# MAX485.net
KiCad netlist of a schematic drawn in Altium Designer
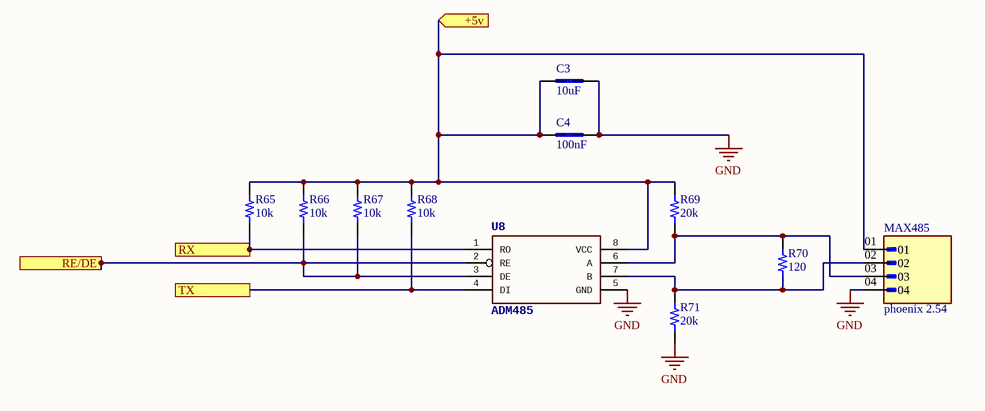
[diagram p0: MAX485.SchDoc]

(export (version "E")
  (design (tool "Eeschema 10.0.6"))
  (components
    (comp (ref "C3")
      (value "10uF")
      (footprint "CAP 0805_2012")
      (description "COMMERCIAL CHIP STD JAPAN BULK - FN TAPE/REEL, 7 INCH PAPER TAPE-0805")
      (fields (field (name "MP") "LD051C182KAB2A"))
      (libsource (lib "cap 0805") (part "LD051C182KAB2A"))
    )
    (comp (ref "C4")
      (value "100nF")
      (footprint "CAP 0805_2012")
      (description "COMMERCIAL CHIP STD JAPAN BULK - FN TAPE/REEL, 7 INCH PAPER TAPE-0805")
      (fields (field (name "MP") "LD051C182KAB2A"))
      (libsource (lib "cap 0805") (part "LD051C182KAB2A"))
    )
    (comp (ref "MAX485")
      (value "phoenix 2.54")
      (footprint "PHOENIX_1881574")
      (fields (field (name "MF") "{'manufacturer': u'Phoenix Contact'}") (field (name "MP") "1881574"))
      (libsource (lib "1881574") (part "1881574"))
    )
    (comp (ref "R65")
      (value "10k")
      (footprint "RES 0805_2012")
      (description "SMT Resistor")
      (libsource (lib "Resistor") (part "Res 0805"))
    )
    (comp (ref "R66")
      (value "10k")
      (footprint "RES 0805_2012")
      (description "SMT Resistor")
      (libsource (lib "Resistor") (part "Res 0805"))
    )
    (comp (ref "R67")
      (value "10k")
      (footprint "RES 0805_2012")
      (description "SMT Resistor")
      (libsource (lib "Resistor") (part "Res 0805"))
    )
    (comp (ref "R68")
      (value "10k")
      (footprint "RES 0805_2012")
      (description "SMT Resistor")
      (libsource (lib "Resistor") (part "Res 0805"))
    )
    (comp (ref "R69")
      (value "20k")
      (footprint "RES 0805_2012")
      (description "SMT Resistor")
      (libsource (lib "Resistor") (part "Res 0805"))
    )
    (comp (ref "R70")
      (value "120")
      (footprint "RES 0805_2012")
      (description "SMT Resistor")
      (libsource (lib "Resistor") (part "Res 0805"))
    )
    (comp (ref "R71")
      (value "20k")
      (footprint "RES 0805_2012")
      (description "SMT Resistor")
      (libsource (lib "Resistor") (part "Res 0805"))
    )
    (comp (ref "U8")
      (value "ADM485")
      (footprint "SOIC-8 4.9X3.9MM P1.27MM")
      (description "RS485 Interface")
      (fields (field (name "PARTNUMBER") "ADM4853ARZ-REEL7"))
      (libsource (lib "Chip") (part "ADM485 (SMD)"))
    )
  )
  (nets
    (net (code "1") (name "/+5v") (class "Default")
      (node (ref "C3") (pin "2") (pinfunction "2_2") (pintype "passive"))
      (node (ref "C4") (pin "2") (pinfunction "2_2") (pintype "passive"))
      (node (ref "MAX485") (pin "01") (pinfunction "01_01") (pintype "passive"))
      (node (ref "R65") (pin "2") (pinfunction "2_2") (pintype "passive"))
      (node (ref "R66") (pin "2") (pinfunction "2_2") (pintype "passive"))
      (node (ref "R67") (pin "2") (pinfunction "2_2") (pintype "passive"))
      (node (ref "R68") (pin "2") (pinfunction "2_2") (pintype "passive"))
      (node (ref "R69") (pin "2") (pinfunction "2_2") (pintype "passive"))
      (node (ref "U8") (pin "8") (pinfunction "VCC_8") (pintype "passive"))
    )
    (net (code "2") (name "/RE{slash}DE") (class "Default")
      (node (ref "R66") (pin "1") (pinfunction "1_1") (pintype "passive"))
      (node (ref "R67") (pin "1") (pinfunction "1_1") (pintype "passive"))
      (node (ref "U8") (pin "2") (pinfunction "RE_2") (pintype "passive"))
      (node (ref "U8") (pin "3") (pinfunction "DE_3") (pintype "passive"))
    )
    (net (code "3") (name "/RX") (class "Default")
      (node (ref "R65") (pin "1") (pinfunction "1_1") (pintype "passive"))
      (node (ref "U8") (pin "1") (pinfunction "RO_1") (pintype "passive"))
    )
    (net (code "4") (name "/TX") (class "Default")
      (node (ref "R68") (pin "1") (pinfunction "1_1") (pintype "passive"))
      (node (ref "U8") (pin "4") (pinfunction "DI_4") (pintype "passive"))
    )
    (net (code "5") (name "GND") (class "Default")
      (node (ref "C3") (pin "1") (pinfunction "1_1") (pintype "passive"))
      (node (ref "C4") (pin "1") (pinfunction "1_1") (pintype "passive"))
      (node (ref "MAX485") (pin "04") (pinfunction "04_04") (pintype "passive"))
      (node (ref "R71") (pin "1") (pinfunction "1_1") (pintype "passive"))
      (node (ref "U8") (pin "5") (pinfunction "GND_5") (pintype "passive"))
    )
    (net (code "6") (name "Net-(U8-A)") (class "Default")
      (node (ref "MAX485") (pin "03") (pinfunction "03_03") (pintype "passive"))
      (node (ref "R69") (pin "1") (pinfunction "1_1") (pintype "passive"))
      (node (ref "R70") (pin "2") (pinfunction "2_2") (pintype "passive"))
      (node (ref "U8") (pin "6") (pinfunction "A_6") (pintype "passive"))
    )
    (net (code "7") (name "Net-(U8-B)") (class "Default")
      (node (ref "MAX485") (pin "02") (pinfunction "02_02") (pintype "passive"))
      (node (ref "R70") (pin "1") (pinfunction "1_1") (pintype "passive"))
      (node (ref "R71") (pin "2") (pinfunction "2_2") (pintype "passive"))
      (node (ref "U8") (pin "7") (pinfunction "B_7") (pintype "passive"))
    )
  )
)
